# Connectors.net
KiCad netlist of a schematic drawn in Altium Designer
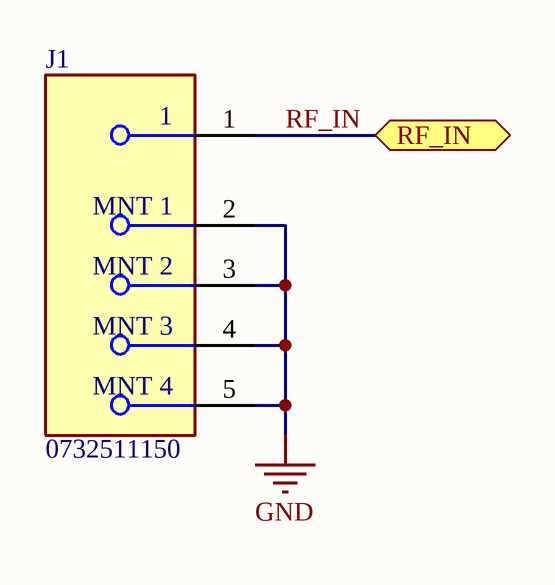
[diagram p0: Connectors.SchDoc]

(export (version "E")
  (design (tool "Eeschema 10.0.6"))
  (components
    (comp (ref "J1")
      (value "0732511150")
      (footprint "FP-0732511150-MFG")
      (description "RF/COAXIAL SMA JACK STR 50OHM EDGE MOUNT")
      (fields (field (name "MANUFACTURER") "Molex Inc"))
      (libsource (lib "Altium Content Vault") (part "2361b00c12d1e236ec859c20ad68b22"))
    )
  )
  (nets
    (net (code "1") (name "/RF_IN") (class "Default")
      (node (ref "J1") (pin "1") (pinfunction "1_1") (pintype "passive"))
    )
    (net (code "2") (name "GND") (class "Default")
      (node (ref "J1") (pin "2") (pinfunction "MNT_1_2") (pintype "passive"))
      (node (ref "J1") (pin "3") (pinfunction "MNT_2_3") (pintype "passive"))
      (node (ref "J1") (pin "4") (pinfunction "MNT_3_4") (pintype "passive"))
      (node (ref "J1") (pin "5") (pinfunction "MNT_4_5") (pintype "passive"))
    )
  )
)
